# WGPS_Featherwing.net
KiCad netlist of a schematic drawn in EAGLE
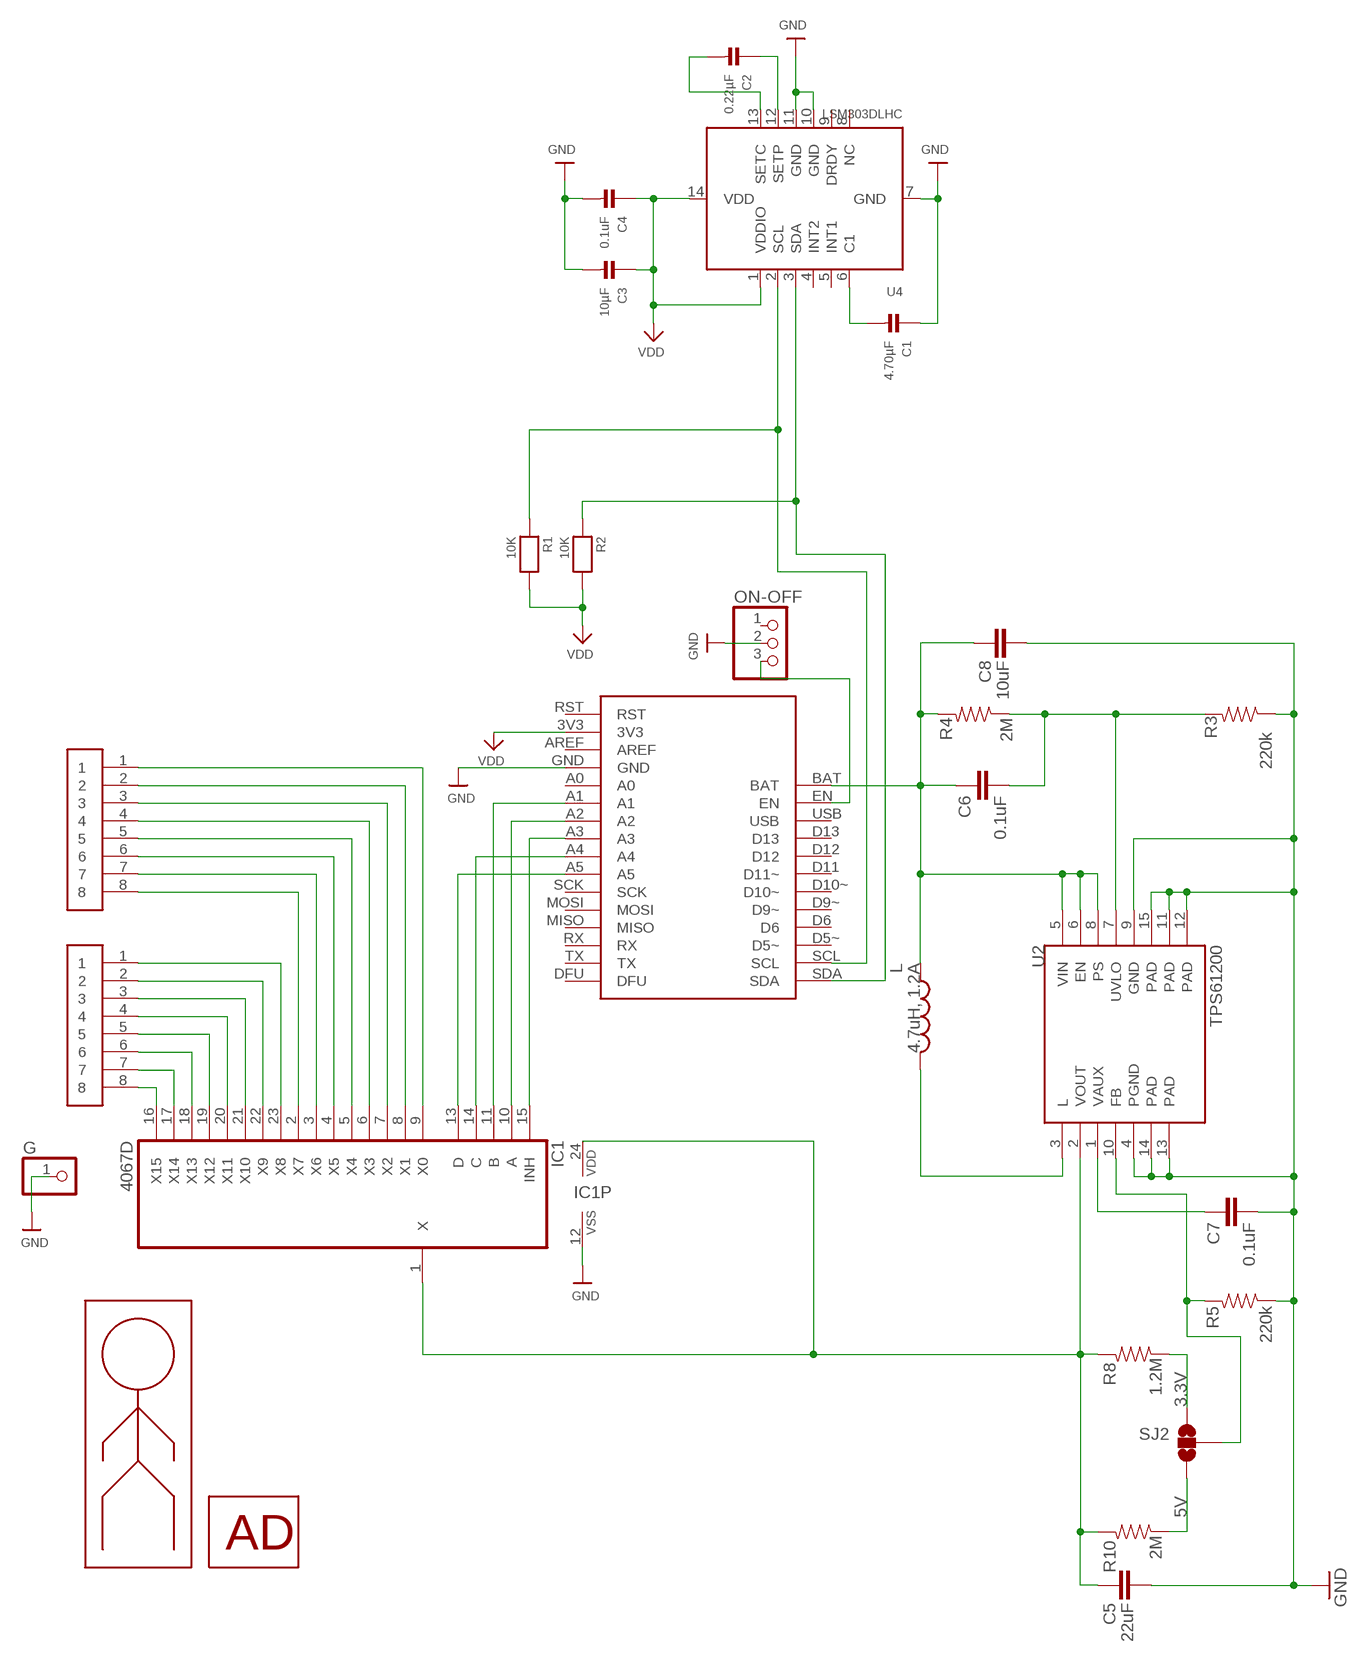
[diagram p0: schematic, sheet 1]

(export (version "E")
  (design (tool "Eeschema 10.0.6"))
  (components
    (comp (ref "C1")
      (value "4.70µF")
      (footprint "eagle-import:_0805")
      (libsource (lib "eagle-import") (part "CAP_CERAMIC_0805"))
    )
    (comp (ref "C2")
      (value "0.22µF")
      (footprint "eagle-import:_0805")
      (libsource (lib "eagle-import") (part "CAP_CERAMIC_0805"))
    )
    (comp (ref "C3")
      (value "10µF")
      (footprint "eagle-import:_0805")
      (libsource (lib "eagle-import") (part "CAP_CERAMIC_0805"))
    )
    (comp (ref "C4")
      (value "0.1uF")
      (footprint "eagle-import:_0805")
      (libsource (lib "eagle-import") (part "CAP_CERAMIC_0805"))
    )
    (comp (ref "C5")
      (value "22uF")
      (footprint "eagle-import:0805")
      (libsource (lib "eagle-import") (part "CAP0805"))
    )
    (comp (ref "C6")
      (value "0.1uF")
      (footprint "eagle-import:0603-CAP")
      (libsource (lib "eagle-import") (part "CAP0603-CAP"))
    )
    (comp (ref "C7")
      (value "0.1uF")
      (footprint "eagle-import:0603-CAP")
      (libsource (lib "eagle-import") (part "CAP0603-CAP"))
    )
    (comp (ref "C8")
      (value "10uF")
      (footprint "eagle-import:1206")
      (libsource (lib "eagle-import") (part "CAP1206"))
    )
    (comp (ref "G")
      (value "PINHD-1X1CB")
      (footprint "eagle-import:1X01-CLEANBIG")
      (libsource (lib "eagle-import") (part "PINHD-1X1CB"))
    )
    (comp (ref "IC1")
      (value "4067D")
      (footprint "eagle-import:SO24W")
      (libsource (lib "eagle-import") (part "4067D"))
    )
    (comp (ref "L")
      (value "4.7uH, 1.2A")
      (footprint "eagle-import:CDRH2D09")
      (libsource (lib "eagle-import") (part "INDUCTOR."))
    )
    (comp (ref "ON-OFF")
      (value "UXCELL_SWITCHCB")
      (footprint "eagle-import:1X03-CLEANBIG")
      (libsource (lib "eagle-import") (part "UXCELL_SWITCHCB"))
    )
    (comp (ref "R1")
      (value "10K")
      (footprint "eagle-import:_0805")
      (libsource (lib "eagle-import") (part "RESISTOR_0805"))
    )
    (comp (ref "R2")
      (value "10K")
      (footprint "eagle-import:_0805")
      (libsource (lib "eagle-import") (part "RESISTOR_0805"))
    )
    (comp (ref "R3")
      (value "220k")
      (footprint "eagle-import:0603-RES")
      (libsource (lib "eagle-import") (part "RESISTOR0603-RES"))
    )
    (comp (ref "R4")
      (value "2M")
      (footprint "eagle-import:0603-RES")
      (libsource (lib "eagle-import") (part "RESISTOR0603-RES"))
    )
    (comp (ref "R5")
      (value "220k")
      (footprint "eagle-import:0603-RES")
      (libsource (lib "eagle-import") (part "RESISTOR0603-RES"))
    )
    (comp (ref "R8")
      (value "1.2M")
      (footprint "eagle-import:0603-RES")
      (libsource (lib "eagle-import") (part "RESISTOR0603-RES"))
    )
    (comp (ref "R10")
      (value "2M")
      (footprint "eagle-import:0603-RES")
      (libsource (lib "eagle-import") (part "RESISTOR0603-RES"))
    )
    (comp (ref "SJ2")
      (value "SOLDERJUMPER_2WAYPASTE2&3")
      (footprint "eagle-import:SJ_3_PASTE2&3")
      (libsource (lib "eagle-import") (part "SOLDERJUMPER_2WAYPASTE2&3"))
    )
    (comp (ref "U$1")
      (value "SMD_FEATHERWING_BLE_32U4")
      (footprint "eagle-import:FEATHERWING_MALE_SMD_HEADERS_0.1")
      (libsource (lib "eagle-import") (part "SMD_FEATHERWING_BLE_32U4"))
    )
    (comp (ref "U$3")
      (value "AD_LOGO")
      (footprint "eagle-import:AD_LOGO_0.25IN")
      (libsource (lib "eagle-import") (part "AD_LOGO"))
    )
    (comp (ref "U$6")
      (value "SMD_JST_1X8")
      (footprint "eagle-import:SMD_JST_1X8")
      (libsource (lib "eagle-import") (part "SMD_JST_1X8"))
    )
    (comp (ref "U$7")
      (value "SMD_JST_1X8")
      (footprint "eagle-import:SMD_JST_1X8")
      (libsource (lib "eagle-import") (part "SMD_JST_1X8"))
    )
    (comp (ref "U$16")
      (value "MAN_LOGO")
      (footprint "eagle-import:MAN_LOGO_0.6")
      (libsource (lib "eagle-import") (part "MAN_LOGO"))
    )
    (comp (ref "U2")
      (value "TPS61200")
      (footprint "eagle-import:QFN-10_PAD")
      (libsource (lib "eagle-import") (part "TPS61200"))
    )
    (comp (ref "U4")
      (value "LSM303DLHC")
      (footprint "eagle-import:LGA14")
      (libsource (lib "eagle-import") (part "LSM303DLHC"))
    )
  )
  (nets
    (net (code "1") (name "/3.3V") (class "Default")
      (node (ref "R8") (pin "1") (pinfunction "1_1") (pintype "passive"))
      (node (ref "SJ2") (pin "1") (pinfunction "1_1") (pintype "passive"))
    )
    (net (code "2") (name "/5V") (class "Default")
      (node (ref "R10") (pin "1") (pinfunction "1_1") (pintype "passive"))
      (node (ref "SJ2") (pin "3") (pinfunction "3_3") (pintype "passive"))
    )
    (net (code "3") (name "GND") (class "Default")
      (node (ref "C1") (pin "1") (pinfunction "P$1_1") (pintype "passive"))
      (node (ref "C3") (pin "2") (pinfunction "P$2_2") (pintype "passive"))
      (node (ref "C4") (pin "2") (pinfunction "P$2_2") (pintype "passive"))
      (node (ref "C5") (pin "2") (pinfunction "2_2") (pintype "passive"))
      (node (ref "C7") (pin "2") (pinfunction "2_2") (pintype "passive"))
      (node (ref "C8") (pin "2") (pinfunction "2_2") (pintype "passive"))
      (node (ref "G") (pin "1") (pinfunction "1_1") (pintype "passive"))
      (node (ref "IC1") (pin "12") (pinfunction "VSS_12") (pintype "power_in"))
      (node (ref "ON-OFF") (pin "2") (pinfunction "2_2") (pintype "passive"))
      (node (ref "R3") (pin "1") (pinfunction "1_1") (pintype "passive"))
      (node (ref "R5") (pin "1") (pinfunction "1_1") (pintype "passive"))
      (node (ref "U$1") (pin "GND") (pinfunction "GND_GND") (pintype "bidirectional"))
      (node (ref "U2") (pin "11") (pinfunction "PAD_11") (pintype "power_in"))
      (node (ref "U2") (pin "12") (pinfunction "PAD_12") (pintype "power_in"))
      (node (ref "U2") (pin "13") (pinfunction "PAD_13") (pintype "power_in"))
      (node (ref "U2") (pin "14") (pinfunction "PAD_14") (pintype "power_in"))
      (node (ref "U2") (pin "15") (pinfunction "PAD_15") (pintype "power_in"))
      (node (ref "U2") (pin "4") (pinfunction "PGND_4") (pintype "power_in"))
      (node (ref "U2") (pin "9") (pinfunction "GND_9") (pintype "power_in"))
      (node (ref "U4") (pin "10") (pinfunction "GND_10") (pintype "power_in"))
      (node (ref "U4") (pin "11") (pinfunction "GND_11") (pintype "power_in"))
      (node (ref "U4") (pin "7") (pinfunction "GND_7") (pintype "power_in"))
    )
    (net (code "4") (name "Net-(C1-P$2)") (class "Default")
      (node (ref "C1") (pin "2") (pinfunction "P$2_2") (pintype "passive"))
      (node (ref "U4") (pin "6") (pinfunction "C1_6") (pintype "bidirectional"))
    )
    (net (code "5") (name "Net-(C2-P$1)") (class "Default")
      (node (ref "C2") (pin "1") (pinfunction "P$1_1") (pintype "passive"))
      (node (ref "U4") (pin "12") (pinfunction "SETP_12") (pintype "bidirectional"))
    )
    (net (code "6") (name "Net-(C2-P$2)") (class "Default")
      (node (ref "C2") (pin "2") (pinfunction "P$2_2") (pintype "passive"))
      (node (ref "U4") (pin "13") (pinfunction "SETC_13") (pintype "bidirectional"))
    )
    (net (code "7") (name "Net-(IC1A-A)") (class "Default")
      (node (ref "IC1") (pin "10") (pinfunction "A_10") (pintype "input"))
      (node (ref "U$1") (pin "A2") (pinfunction "A2_A2") (pintype "bidirectional"))
    )
    (net (code "8") (name "Net-(IC1A-B)") (class "Default")
      (node (ref "IC1") (pin "11") (pinfunction "B_11") (pintype "input"))
      (node (ref "U$1") (pin "A1") (pinfunction "A1_A1") (pintype "bidirectional"))
    )
    (net (code "9") (name "Net-(IC1A-C)") (class "Default")
      (node (ref "IC1") (pin "14") (pinfunction "C_14") (pintype "input"))
      (node (ref "U$1") (pin "A4") (pinfunction "A4_A4") (pintype "bidirectional"))
    )
    (net (code "10") (name "Net-(IC1A-D)") (class "Default")
      (node (ref "IC1") (pin "13") (pinfunction "D_13") (pintype "input"))
      (node (ref "U$1") (pin "A5") (pinfunction "A5_A5") (pintype "bidirectional"))
    )
    (net (code "11") (name "Net-(IC1A-INH)") (class "Default")
      (node (ref "IC1") (pin "15") (pinfunction "INH_15") (pintype "input"))
      (node (ref "U$1") (pin "A3") (pinfunction "A3_A3") (pintype "bidirectional"))
    )
    (net (code "12") (name "Net-(IC1A-X)") (class "Default")
      (node (ref "C5") (pin "1") (pinfunction "1_1") (pintype "passive"))
      (node (ref "IC1") (pin "1") (pinfunction "X_1") (pintype "output"))
      (node (ref "IC1") (pin "24") (pinfunction "VDD_24") (pintype "power_in"))
      (node (ref "R10") (pin "2") (pinfunction "2_2") (pintype "passive"))
      (node (ref "R8") (pin "2") (pinfunction "2_2") (pintype "passive"))
      (node (ref "U2") (pin "2") (pinfunction "VOUT_2") (pintype "passive"))
    )
    (net (code "13") (name "Net-(IC1A-X0)") (class "Default")
      (node (ref "IC1") (pin "9") (pinfunction "X0_9") (pintype "input"))
      (node (ref "U$6") (pin "1") (pinfunction "1_1") (pintype "bidirectional"))
    )
    (net (code "14") (name "Net-(IC1A-X1)") (class "Default")
      (node (ref "IC1") (pin "8") (pinfunction "X1_8") (pintype "input"))
      (node (ref "U$6") (pin "2") (pinfunction "2_2") (pintype "bidirectional"))
    )
    (net (code "15") (name "Net-(IC1A-X2)") (class "Default")
      (node (ref "IC1") (pin "7") (pinfunction "X2_7") (pintype "input"))
      (node (ref "U$6") (pin "3") (pinfunction "3_3") (pintype "bidirectional"))
    )
    (net (code "16") (name "Net-(IC1A-X3)") (class "Default")
      (node (ref "IC1") (pin "6") (pinfunction "X3_6") (pintype "input"))
      (node (ref "U$6") (pin "4") (pinfunction "4_4") (pintype "bidirectional"))
    )
    (net (code "17") (name "Net-(IC1A-X4)") (class "Default")
      (node (ref "IC1") (pin "5") (pinfunction "X4_5") (pintype "input"))
      (node (ref "U$6") (pin "5") (pinfunction "5_5") (pintype "bidirectional"))
    )
    (net (code "18") (name "Net-(IC1A-X5)") (class "Default")
      (node (ref "IC1") (pin "4") (pinfunction "X5_4") (pintype "input"))
      (node (ref "U$6") (pin "6") (pinfunction "6_6") (pintype "bidirectional"))
    )
    (net (code "19") (name "Net-(IC1A-X6)") (class "Default")
      (node (ref "IC1") (pin "3") (pinfunction "X6_3") (pintype "input"))
      (node (ref "U$6") (pin "7") (pinfunction "7_7") (pintype "bidirectional"))
    )
    (net (code "20") (name "Net-(IC1A-X7)") (class "Default")
      (node (ref "IC1") (pin "2") (pinfunction "X7_2") (pintype "input"))
      (node (ref "U$6") (pin "8") (pinfunction "8_8") (pintype "bidirectional"))
    )
    (net (code "21") (name "Net-(IC1A-X8)") (class "Default")
      (node (ref "IC1") (pin "23") (pinfunction "X8_23") (pintype "input"))
      (node (ref "U$7") (pin "1") (pinfunction "1_1") (pintype "bidirectional"))
    )
    (net (code "22") (name "Net-(IC1A-X9)") (class "Default")
      (node (ref "IC1") (pin "22") (pinfunction "X9_22") (pintype "input"))
      (node (ref "U$7") (pin "2") (pinfunction "2_2") (pintype "bidirectional"))
    )
    (net (code "23") (name "Net-(IC1A-X10)") (class "Default")
      (node (ref "IC1") (pin "21") (pinfunction "X10_21") (pintype "input"))
      (node (ref "U$7") (pin "3") (pinfunction "3_3") (pintype "bidirectional"))
    )
    (net (code "24") (name "Net-(IC1A-X11)") (class "Default")
      (node (ref "IC1") (pin "20") (pinfunction "X11_20") (pintype "input"))
      (node (ref "U$7") (pin "4") (pinfunction "4_4") (pintype "bidirectional"))
    )
    (net (code "25") (name "Net-(IC1A-X12)") (class "Default")
      (node (ref "IC1") (pin "19") (pinfunction "X12_19") (pintype "input"))
      (node (ref "U$7") (pin "5") (pinfunction "5_5") (pintype "bidirectional"))
    )
    (net (code "26") (name "Net-(IC1A-X13)") (class "Default")
      (node (ref "IC1") (pin "18") (pinfunction "X13_18") (pintype "input"))
      (node (ref "U$7") (pin "6") (pinfunction "6_6") (pintype "bidirectional"))
    )
    (net (code "27") (name "Net-(IC1A-X14)") (class "Default")
      (node (ref "IC1") (pin "17") (pinfunction "X14_17") (pintype "input"))
      (node (ref "U$7") (pin "7") (pinfunction "7_7") (pintype "bidirectional"))
    )
    (net (code "28") (name "Net-(IC1A-X15)") (class "Default")
      (node (ref "IC1") (pin "16") (pinfunction "X15_16") (pintype "input"))
      (node (ref "U$7") (pin "8") (pinfunction "8_8") (pintype "bidirectional"))
    )
    (net (code "29") (name "Net-(L-1)") (class "Default")
      (node (ref "L") (pin "P$1") (pinfunction "1_P$1") (pintype "passive"))
      (node (ref "U2") (pin "3") (pinfunction "L_3") (pintype "passive"))
    )
    (net (code "30") (name "Net-(L-2)") (class "Default")
      (node (ref "C6") (pin "1") (pinfunction "1_1") (pintype "passive"))
      (node (ref "C8") (pin "1") (pinfunction "1_1") (pintype "passive"))
      (node (ref "L") (pin "P$2") (pinfunction "2_P$2") (pintype "passive"))
      (node (ref "R4") (pin "2") (pinfunction "2_2") (pintype "passive"))
      (node (ref "U$1") (pin "BAT") (pinfunction "BAT_BAT") (pintype "bidirectional"))
      (node (ref "U2") (pin "5") (pinfunction "VIN_5") (pintype "power_in"))
      (node (ref "U2") (pin "6") (pinfunction "EN_6") (pintype "input"))
      (node (ref "U2") (pin "8") (pinfunction "PS_8") (pintype "input"))
    )
    (net (code "31") (name "Net-(ON-OFF-Pad3)") (class "Default")
      (node (ref "ON-OFF") (pin "3") (pinfunction "3_3") (pintype "passive"))
      (node (ref "U$1") (pin "EN") (pinfunction "EN_EN") (pintype "bidirectional"))
    )
    (net (code "32") (name "Net-(U2-FB)") (class "Default")
      (node (ref "R5") (pin "2") (pinfunction "2_2") (pintype "passive"))
      (node (ref "SJ2") (pin "2") (pinfunction "2_2") (pintype "passive"))
      (node (ref "U2") (pin "10") (pinfunction "FB_10") (pintype "passive"))
    )
    (net (code "33") (name "Net-(U2-UVLO)") (class "Default")
      (node (ref "C6") (pin "2") (pinfunction "2_2") (pintype "passive"))
      (node (ref "R3") (pin "2") (pinfunction "2_2") (pintype "passive"))
      (node (ref "R4") (pin "1") (pinfunction "1_1") (pintype "passive"))
      (node (ref "U2") (pin "7") (pinfunction "UVLO_7") (pintype "passive"))
    )
    (net (code "34") (name "Net-(U2-VAUX)") (class "Default")
      (node (ref "C7") (pin "1") (pinfunction "1_1") (pintype "passive"))
      (node (ref "U2") (pin "1") (pinfunction "VAUX_1") (pintype "passive"))
    )
    (net (code "35") (name "Net-(U4-SCL)") (class "Default")
      (node (ref "R1") (pin "1") (pinfunction "1_1") (pintype "passive"))
      (node (ref "U$1") (pin "SCL") (pinfunction "SCL_SCL") (pintype "bidirectional"))
      (node (ref "U4") (pin "2") (pinfunction "SCL_2") (pintype "bidirectional"))
    )
    (net (code "36") (name "Net-(U4-SDA)") (class "Default")
      (node (ref "R2") (pin "1") (pinfunction "1_1") (pintype "passive"))
      (node (ref "U$1") (pin "SDA") (pinfunction "SDA_SDA") (pintype "bidirectional"))
      (node (ref "U4") (pin "3") (pinfunction "SDA_3") (pintype "bidirectional"))
    )
    (net (code "37") (name "VDD") (class "Default")
      (node (ref "C3") (pin "1") (pinfunction "P$1_1") (pintype "passive"))
      (node (ref "C4") (pin "1") (pinfunction "P$1_1") (pintype "passive"))
      (node (ref "R1") (pin "2") (pinfunction "2_2") (pintype "passive"))
      (node (ref "R2") (pin "2") (pinfunction "2_2") (pintype "passive"))
      (node (ref "U$1") (pin "3V3") (pinfunction "3V3_3V3") (pintype "bidirectional"))
      (node (ref "U4") (pin "1") (pinfunction "VDDIO_1") (pintype "power_in"))
      (node (ref "U4") (pin "14") (pinfunction "VDD_14") (pintype "power_in"))
    )
    (net (code "38") (name "unconnected-(ON-OFF-Pad1)") (class "Default")
      (node (ref "ON-OFF") (pin "1") (pinfunction "1_1") (pintype "passive"))
    )
    (net (code "39") (name "unconnected-(U$1-D5~{}-PadD5~)") (class "Default")
      (node (ref "U$1") (pin "D5~") (pinfunction "D5~{}_D5~") (pintype "bidirectional"))
    )
    (net (code "40") (name "unconnected-(U$1-D9~{}-PadD9~)") (class "Default")
      (node (ref "U$1") (pin "D9~") (pinfunction "D9~{}_D9~") (pintype "bidirectional"))
    )
    (net (code "41") (name "unconnected-(U$1-D10~{}-PadD10~)") (class "Default")
      (node (ref "U$1") (pin "D10~") (pinfunction "D10~{}_D10~") (pintype "bidirectional"))
    )
    (net (code "42") (name "unconnected-(U$1-D11~{}-PadD11)") (class "Default")
      (node (ref "U$1") (pin "D11") (pinfunction "D11~{}_D11") (pintype "bidirectional"))
    )
    (net (code "43") (name "unconnected-(U$1-PadA0)") (class "Default")
      (node (ref "U$1") (pin "A0") (pinfunction "A0_A0") (pintype "bidirectional"))
    )
    (net (code "44") (name "unconnected-(U$1-PadAREF)") (class "Default")
      (node (ref "U$1") (pin "AREF") (pinfunction "AREF_AREF") (pintype "bidirectional"))
    )
    (net (code "45") (name "unconnected-(U$1-PadD6)") (class "Default")
      (node (ref "U$1") (pin "D6") (pinfunction "D6_D6") (pintype "bidirectional"))
    )
    (net (code "46") (name "unconnected-(U$1-PadD12)") (class "Default")
      (node (ref "U$1") (pin "D12") (pinfunction "D12_D12") (pintype "bidirectional"))
    )
    (net (code "47") (name "unconnected-(U$1-PadD13)") (class "Default")
      (node (ref "U$1") (pin "D13") (pinfunction "D13_D13") (pintype "bidirectional"))
    )
    (net (code "48") (name "unconnected-(U$1-PadDFU)") (class "Default")
      (node (ref "U$1") (pin "DFU") (pinfunction "DFU_DFU") (pintype "bidirectional"))
    )
    (net (code "49") (name "unconnected-(U$1-PadMISO)") (class "Default")
      (node (ref "U$1") (pin "MISO") (pinfunction "MISO_MISO") (pintype "bidirectional"))
    )
    (net (code "50") (name "unconnected-(U$1-PadMOSI)") (class "Default")
      (node (ref "U$1") (pin "MOSI") (pinfunction "MOSI_MOSI") (pintype "bidirectional"))
    )
    (net (code "51") (name "unconnected-(U$1-PadRST)") (class "Default")
      (node (ref "U$1") (pin "RST") (pinfunction "RST_RST") (pintype "bidirectional"))
    )
    (net (code "52") (name "unconnected-(U$1-PadRX)") (class "Default")
      (node (ref "U$1") (pin "RX") (pinfunction "RX_RX") (pintype "bidirectional"))
    )
    (net (code "53") (name "unconnected-(U$1-PadSCK)") (class "Default")
      (node (ref "U$1") (pin "SCK") (pinfunction "SCK_SCK") (pintype "bidirectional"))
    )
    (net (code "54") (name "unconnected-(U$1-PadTX)") (class "Default")
      (node (ref "U$1") (pin "TX") (pinfunction "TX_TX") (pintype "bidirectional"))
    )
    (net (code "55") (name "unconnected-(U$1-PadUSB)") (class "Default")
      (node (ref "U$1") (pin "USB") (pinfunction "USB_USB") (pintype "bidirectional"))
    )
    (net (code "56") (name "unconnected-(U4-DRDY-Pad9)") (class "Default")
      (node (ref "U4") (pin "9") (pinfunction "DRDY_9") (pintype "output"))
    )
    (net (code "57") (name "unconnected-(U4-INT1-Pad5)") (class "Default")
      (node (ref "U4") (pin "5") (pinfunction "INT1_5") (pintype "output"))
    )
    (net (code "58") (name "unconnected-(U4-INT2-Pad4)") (class "Default")
      (node (ref "U4") (pin "4") (pinfunction "INT2_4") (pintype "output"))
    )
    (net (code "59") (name "unconnected-(U4-NC-Pad8)") (class "Default")
      (node (ref "U4") (pin "8") (pinfunction "NC_8") (pintype "bidirectional"))
    )
  )
)
